# 04_GIRIS_CIKIS_EMG_BUTTONS.net
KiCad netlist of a schematic drawn in Altium Designer
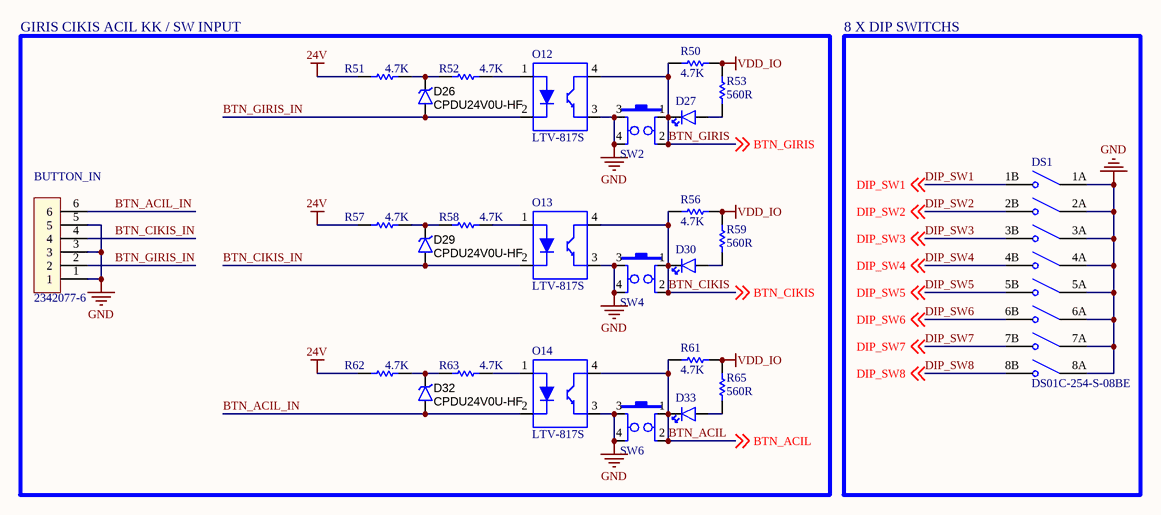
[diagram p0: 04_GIRIS_CIKIS_EMG_BUTTONS.SchDoc]

(export (version "E")
  (design (tool "Eeschema 10.0.6"))
  (components
    (comp (ref "BUTTON_IN")
      (value "2342077-6")
      (footprint "TERM BLOCK HDR 6POS 90DEG PITCH 3.81MM")
      (fields
        (field (name "DIGI-KEY PART NUMBER") "A145325-ND")
        (field (name "MANUFACTURER") "TE Connectivity AMP Connectors")
      )
      (libsource (lib "FKDZ_Altium_Lib") (part "TERM BLOCK HDR 6POS 90DEG 3.81MM"))
    )
    (comp (ref "D26")
      (value "CPDU24V0U-HF")
      (footprint "SOD523F")
      (description "50V Clamp 3A (8/20µs) Ipp Tvs Diode Surface Mount 0603/SOD-523F")
      (fields
        (field (name "DIGI-KEY PART NUMBER") "641-1679-1-ND")
        (field (name "MANUFACTURER") "Comchip Technology")
      )
      (libsource (lib "FKDZ_Altium_Lib") (part "TVS DIODE 24VWM 50V 0603/SOD523F CPDU24V0U-HF"))
    )
    (comp (ref "D27")
      (value "led_green")
      (footprint "805LED")
      (description "LED 2X1.2MM 570NM GN WTR CLR SMD")
      (fields (field (name "DIGI-KEY PART NUMBER") "754-1127-1-ND"))
      (libsource (lib "FKDZ_Altium_Lib") (part "LED_GREEN_0805"))
    )
    (comp (ref "D29")
      (value "CPDU24V0U-HF")
      (footprint "SOD523F")
      (description "50V Clamp 3A (8/20µs) Ipp Tvs Diode Surface Mount 0603/SOD-523F")
      (fields
        (field (name "DIGI-KEY PART NUMBER") "641-1679-1-ND")
        (field (name "MANUFACTURER") "Comchip Technology")
      )
      (libsource (lib "FKDZ_Altium_Lib") (part "TVS DIODE 24VWM 50V 0603/SOD523F CPDU24V0U-HF"))
    )
    (comp (ref "D30")
      (value "led_green")
      (footprint "805LED")
      (description "LED 2X1.2MM 570NM GN WTR CLR SMD")
      (fields (field (name "DIGI-KEY PART NUMBER") "754-1127-1-ND"))
      (libsource (lib "FKDZ_Altium_Lib") (part "LED_GREEN_0805"))
    )
    (comp (ref "D32")
      (value "CPDU24V0U-HF")
      (footprint "SOD523F")
      (description "50V Clamp 3A (8/20µs) Ipp Tvs Diode Surface Mount 0603/SOD-523F")
      (fields
        (field (name "DIGI-KEY PART NUMBER") "641-1679-1-ND")
        (field (name "MANUFACTURER") "Comchip Technology")
      )
      (libsource (lib "FKDZ_Altium_Lib") (part "TVS DIODE 24VWM 50V 0603/SOD523F CPDU24V0U-HF"))
    )
    (comp (ref "D33")
      (value "led_green")
      (footprint "805LED")
      (description "LED 2X1.2MM 570NM GN WTR CLR SMD")
      (fields (field (name "DIGI-KEY PART NUMBER") "754-1127-1-ND"))
      (libsource (lib "FKDZ_Altium_Lib") (part "LED_GREEN_0805"))
    )
    (comp (ref "DS1")
      (value "DS01C-254-S-08BE")
      (footprint "SW_DS01C-254-S-08BE")
      (description "Dip Switch SPST 8 Position Through Hole Slide (Standard) Actuator 25mA 24VDC")
      (fields (field (name "DIGI-KEY PART NUMBER") "2223-DS01C-254-S-08BE-ND"))
      (libsource (lib "FKDZ_Altium_Lib") (part "DIP SWITCH, SPST, 2.54 PITCH, RA DS01C-254-S-08BE"))
    )
    (comp (ref "O12")
      (value "LTV-817S")
      (footprint "SMD4-2.54-4.6X6.5MM")
      (description "Optoisolator Transistor Output 5000Vrms 1 Channel 4-SMD")
      (fields (field (name "DIGI-KEY PART NUMBER") "160-1367-5-ND"))
      (libsource (lib "FKDZ_Altium_Lib") (part "OPTOISOLATR 5KV TRANSISTOR 4-SMD LTV-817S"))
    )
    (comp (ref "O13")
      (value "LTV-817S")
      (footprint "SMD4-2.54-4.6X6.5MM")
      (description "Optoisolator Transistor Output 5000Vrms 1 Channel 4-SMD")
      (fields (field (name "DIGI-KEY PART NUMBER") "160-1367-5-ND"))
      (libsource (lib "FKDZ_Altium_Lib") (part "OPTOISOLATR 5KV TRANSISTOR 4-SMD LTV-817S"))
    )
    (comp (ref "O14")
      (value "LTV-817S")
      (footprint "SMD4-2.54-4.6X6.5MM")
      (description "Optoisolator Transistor Output 5000Vrms 1 Channel 4-SMD")
      (fields (field (name "DIGI-KEY PART NUMBER") "160-1367-5-ND"))
      (libsource (lib "FKDZ_Altium_Lib") (part "OPTOISOLATR 5KV TRANSISTOR 4-SMD LTV-817S"))
    )
    (comp (ref "R50")
      (value "4.7K")
      (footprint "603R")
      (description "4.7 kOhms ±5% 0.1W, 1/10W Chip Resistor 0603 (1608 Metric) Moisture Resistant Thick Film")
      (fields (field (name "DIGI-KEY PART NUMBER") "311-4.7KGRTR-ND") (field (name "MANUFACTURER") "Yageo"))
      (libsource (lib "FKDZ_Altium_Lib") (part "RES_4.7K_OHM_%5_0.1W_0603"))
    )
    (comp (ref "R51")
      (value "4.7K")
      (footprint "603R")
      (description "4.7 kOhms ±5% 0.1W, 1/10W Chip Resistor 0603 (1608 Metric) Moisture Resistant Thick Film")
      (fields (field (name "DIGI-KEY PART NUMBER") "311-4.7KGRTR-ND") (field (name "MANUFACTURER") "Yageo"))
      (libsource (lib "FKDZ_Altium_Lib") (part "RES_4.7K_OHM_%5_0.1W_0603"))
    )
    (comp (ref "R52")
      (value "4.7K")
      (footprint "603R")
      (description "4.7 kOhms ±5% 0.1W, 1/10W Chip Resistor 0603 (1608 Metric) Moisture Resistant Thick Film")
      (fields (field (name "DIGI-KEY PART NUMBER") "311-4.7KGRTR-ND") (field (name "MANUFACTURER") "Yageo"))
      (libsource (lib "FKDZ_Altium_Lib") (part "RES_4.7K_OHM_%5_0.1W_0603"))
    )
    (comp (ref "R53")
      (value "560R")
      (footprint "603R")
      (description "560 Ohms ±5% 0.1W, 1/10W Chip Resistor 0603 (1608 Metric) Moisture Resistant Thick Film")
      (fields (field (name "DIGI-KEY PART NUMBER") "311-560GRCT-ND") (field (name "MANUFACTURER") "Yageo"))
      (libsource (lib "FKDZ_Altium_Lib") (part "RES_560_OHM_%5_0.1W_0603"))
    )
    (comp (ref "R56")
      (value "4.7K")
      (footprint "603R")
      (description "4.7 kOhms ±5% 0.1W, 1/10W Chip Resistor 0603 (1608 Metric) Moisture Resistant Thick Film")
      (fields (field (name "DIGI-KEY PART NUMBER") "311-4.7KGRTR-ND") (field (name "MANUFACTURER") "Yageo"))
      (libsource (lib "FKDZ_Altium_Lib") (part "RES_4.7K_OHM_%5_0.1W_0603"))
    )
    (comp (ref "R57")
      (value "4.7K")
      (footprint "603R")
      (description "4.7 kOhms ±5% 0.1W, 1/10W Chip Resistor 0603 (1608 Metric) Moisture Resistant Thick Film")
      (fields (field (name "DIGI-KEY PART NUMBER") "311-4.7KGRTR-ND") (field (name "MANUFACTURER") "Yageo"))
      (libsource (lib "FKDZ_Altium_Lib") (part "RES_4.7K_OHM_%5_0.1W_0603"))
    )
    (comp (ref "R58")
      (value "4.7K")
      (footprint "603R")
      (description "4.7 kOhms ±5% 0.1W, 1/10W Chip Resistor 0603 (1608 Metric) Moisture Resistant Thick Film")
      (fields (field (name "DIGI-KEY PART NUMBER") "311-4.7KGRTR-ND") (field (name "MANUFACTURER") "Yageo"))
      (libsource (lib "FKDZ_Altium_Lib") (part "RES_4.7K_OHM_%5_0.1W_0603"))
    )
    (comp (ref "R59")
      (value "560R")
      (footprint "603R")
      (description "560 Ohms ±5% 0.1W, 1/10W Chip Resistor 0603 (1608 Metric) Moisture Resistant Thick Film")
      (fields (field (name "DIGI-KEY PART NUMBER") "311-560GRCT-ND") (field (name "MANUFACTURER") "Yageo"))
      (libsource (lib "FKDZ_Altium_Lib") (part "RES_560_OHM_%5_0.1W_0603"))
    )
    (comp (ref "R61")
      (value "4.7K")
      (footprint "603R")
      (description "4.7 kOhms ±5% 0.1W, 1/10W Chip Resistor 0603 (1608 Metric) Moisture Resistant Thick Film")
      (fields (field (name "DIGI-KEY PART NUMBER") "311-4.7KGRTR-ND") (field (name "MANUFACTURER") "Yageo"))
      (libsource (lib "FKDZ_Altium_Lib") (part "RES_4.7K_OHM_%5_0.1W_0603"))
    )
    (comp (ref "R62")
      (value "4.7K")
      (footprint "603R")
      (description "4.7 kOhms ±5% 0.1W, 1/10W Chip Resistor 0603 (1608 Metric) Moisture Resistant Thick Film")
      (fields (field (name "DIGI-KEY PART NUMBER") "311-4.7KGRTR-ND") (field (name "MANUFACTURER") "Yageo"))
      (libsource (lib "FKDZ_Altium_Lib") (part "RES_4.7K_OHM_%5_0.1W_0603"))
    )
    (comp (ref "R63")
      (value "4.7K")
      (footprint "603R")
      (description "4.7 kOhms ±5% 0.1W, 1/10W Chip Resistor 0603 (1608 Metric) Moisture Resistant Thick Film")
      (fields (field (name "DIGI-KEY PART NUMBER") "311-4.7KGRTR-ND") (field (name "MANUFACTURER") "Yageo"))
      (libsource (lib "FKDZ_Altium_Lib") (part "RES_4.7K_OHM_%5_0.1W_0603"))
    )
    (comp (ref "R65")
      (value "560R")
      (footprint "603R")
      (description "560 Ohms ±5% 0.1W, 1/10W Chip Resistor 0603 (1608 Metric) Moisture Resistant Thick Film")
      (fields (field (name "DIGI-KEY PART NUMBER") "311-560GRCT-ND") (field (name "MANUFACTURER") "Yageo"))
      (libsource (lib "FKDZ_Altium_Lib") (part "RES_560_OHM_%5_0.1W_0603"))
    )
    (comp (ref "SW2")
      (value "switch tactile")
      (footprint "SW_TACTILE_6X6mm SMT")
      (description "Tactile Switch SPST-NO Top Actuated Surface Mount")
      (fields (field (name "DIGI-KEY PART NUMBER") "CKN9112TR-ND"))
      (libsource (lib "FKDZ_Altium_Lib") (part "SW_TACTILE_6x6x4.3mm SMT"))
    )
    (comp (ref "SW4")
      (value "switch tactile")
      (footprint "SW_TACTILE_6X6mm SMT")
      (description "Tactile Switch SPST-NO Top Actuated Surface Mount")
      (fields (field (name "DIGI-KEY PART NUMBER") "CKN9112TR-ND"))
      (libsource (lib "FKDZ_Altium_Lib") (part "SW_TACTILE_6x6x4.3mm SMT"))
    )
    (comp (ref "SW6")
      (value "switch tactile")
      (footprint "SW_TACTILE_6X6mm SMT")
      (description "Tactile Switch SPST-NO Top Actuated Surface Mount")
      (fields (field (name "DIGI-KEY PART NUMBER") "CKN9112TR-ND"))
      (libsource (lib "FKDZ_Altium_Lib") (part "SW_TACTILE_6x6x4.3mm SMT"))
    )
  )
  (nets
    (net (code "1") (name "/BTN_ACIL_IN") (class "Default")
      (node (ref "BUTTON_IN") (pin "6") (pinfunction "6_6") (pintype "passive"))
      (node (ref "D32") (pin "1") (pinfunction "1_1") (pintype "passive"))
      (node (ref "O14") (pin "2") (pinfunction "CATHODE_2") (pintype "passive"))
    )
    (net (code "2") (name "/BTN_CIKIS_IN") (class "Default")
      (node (ref "BUTTON_IN") (pin "4") (pinfunction "4_4") (pintype "passive"))
      (node (ref "D29") (pin "1") (pinfunction "1_1") (pintype "passive"))
      (node (ref "O13") (pin "2") (pinfunction "CATHODE_2") (pintype "passive"))
    )
    (net (code "3") (name "/BTN_GIRIS_IN") (class "Default")
      (node (ref "BUTTON_IN") (pin "2") (pinfunction "2_2") (pintype "passive"))
      (node (ref "D26") (pin "1") (pinfunction "1_1") (pintype "passive"))
      (node (ref "O12") (pin "2") (pinfunction "CATHODE_2") (pintype "passive"))
    )
    (net (code "4") (name "24V") (class "Default")
      (node (ref "R51") (pin "1") (pinfunction "1_1") (pintype "passive"))
      (node (ref "R57") (pin "1") (pinfunction "1_1") (pintype "passive"))
      (node (ref "R62") (pin "1") (pinfunction "1_1") (pintype "passive"))
    )
    (net (code "5") (name "BTN_ACIL") (class "Default")
      (node (ref "D33") (pin "2") (pinfunction "K_2") (pintype "passive"))
      (node (ref "O14") (pin "4") (pinfunction "COLLECTOR_4") (pintype "passive"))
      (node (ref "R61") (pin "1") (pinfunction "1_1") (pintype "passive"))
      (node (ref "SW6") (pin "1") (pinfunction "1_1") (pintype "passive"))
      (node (ref "SW6") (pin "2") (pinfunction "2_2") (pintype "passive"))
    )
    (net (code "6") (name "BTN_CIKIS") (class "Default")
      (node (ref "D30") (pin "2") (pinfunction "K_2") (pintype "passive"))
      (node (ref "O13") (pin "4") (pinfunction "COLLECTOR_4") (pintype "passive"))
      (node (ref "R56") (pin "1") (pinfunction "1_1") (pintype "passive"))
      (node (ref "SW4") (pin "1") (pinfunction "1_1") (pintype "passive"))
      (node (ref "SW4") (pin "2") (pinfunction "2_2") (pintype "passive"))
    )
    (net (code "7") (name "BTN_GIRIS") (class "Default")
      (node (ref "D27") (pin "2") (pinfunction "K_2") (pintype "passive"))
      (node (ref "O12") (pin "4") (pinfunction "COLLECTOR_4") (pintype "passive"))
      (node (ref "R50") (pin "1") (pinfunction "1_1") (pintype "passive"))
      (node (ref "SW2") (pin "1") (pinfunction "1_1") (pintype "passive"))
      (node (ref "SW2") (pin "2") (pinfunction "2_2") (pintype "passive"))
    )
    (net (code "8") (name "DIP_SW1") (class "Default")
      (node (ref "DS1") (pin "1B") (pinfunction "NO1_1B") (pintype "passive"))
    )
    (net (code "9") (name "DIP_SW2") (class "Default")
      (node (ref "DS1") (pin "2B") (pinfunction "NO2_2B") (pintype "passive"))
    )
    (net (code "10") (name "DIP_SW3") (class "Default")
      (node (ref "DS1") (pin "3B") (pinfunction "NO3_3B") (pintype "passive"))
    )
    (net (code "11") (name "DIP_SW4") (class "Default")
      (node (ref "DS1") (pin "4B") (pinfunction "NO4_4B") (pintype "passive"))
    )
    (net (code "12") (name "DIP_SW5") (class "Default")
      (node (ref "DS1") (pin "5B") (pinfunction "NO5_5B") (pintype "passive"))
    )
    (net (code "13") (name "DIP_SW6") (class "Default")
      (node (ref "DS1") (pin "6B") (pinfunction "NO6_6B") (pintype "passive"))
    )
    (net (code "14") (name "DIP_SW7") (class "Default")
      (node (ref "DS1") (pin "7B") (pinfunction "NO7_7B") (pintype "passive"))
    )
    (net (code "15") (name "DIP_SW8") (class "Default")
      (node (ref "DS1") (pin "8B") (pinfunction "NO8_8B") (pintype "passive"))
    )
    (net (code "16") (name "GND") (class "Default")
      (node (ref "BUTTON_IN") (pin "1") (pinfunction "1_1") (pintype "passive"))
      (node (ref "BUTTON_IN") (pin "3") (pinfunction "3_3") (pintype "passive"))
      (node (ref "BUTTON_IN") (pin "5") (pinfunction "5_5") (pintype "passive"))
      (node (ref "DS1") (pin "1A") (pinfunction "COM1_1A") (pintype "passive"))
      (node (ref "DS1") (pin "2A") (pinfunction "COM2_2A") (pintype "passive"))
      (node (ref "DS1") (pin "3A") (pinfunction "COM3_3A") (pintype "passive"))
      (node (ref "DS1") (pin "4A") (pinfunction "COM4_4A") (pintype "passive"))
      (node (ref "DS1") (pin "5A") (pinfunction "COM5_5A") (pintype "passive"))
      (node (ref "DS1") (pin "6A") (pinfunction "COM6_6A") (pintype "passive"))
      (node (ref "DS1") (pin "7A") (pinfunction "COM7_7A") (pintype "passive"))
      (node (ref "DS1") (pin "8A") (pinfunction "COM8_8A") (pintype "passive"))
      (node (ref "O12") (pin "3") (pinfunction "EMITER_3") (pintype "passive"))
      (node (ref "O13") (pin "3") (pinfunction "EMITER_3") (pintype "passive"))
      (node (ref "O14") (pin "3") (pinfunction "EMITER_3") (pintype "passive"))
      (node (ref "SW2") (pin "3") (pinfunction "3_3") (pintype "passive"))
      (node (ref "SW2") (pin "4") (pinfunction "4_4") (pintype "passive"))
      (node (ref "SW4") (pin "3") (pinfunction "3_3") (pintype "passive"))
      (node (ref "SW4") (pin "4") (pinfunction "4_4") (pintype "passive"))
      (node (ref "SW6") (pin "3") (pinfunction "3_3") (pintype "passive"))
      (node (ref "SW6") (pin "4") (pinfunction "4_4") (pintype "passive"))
    )
    (net (code "17") (name "Net-(D26-Pad2)") (class "Default")
      (node (ref "D26") (pin "2") (pinfunction "2_2") (pintype "passive"))
      (node (ref "R51") (pin "2") (pinfunction "2_2") (pintype "passive"))
      (node (ref "R52") (pin "1") (pinfunction "1_1") (pintype "passive"))
    )
    (net (code "18") (name "Net-(D27-A)") (class "Default")
      (node (ref "D27") (pin "1") (pinfunction "A_1") (pintype "passive"))
      (node (ref "R53") (pin "1") (pinfunction "1_1") (pintype "passive"))
    )
    (net (code "19") (name "Net-(D29-Pad2)") (class "Default")
      (node (ref "D29") (pin "2") (pinfunction "2_2") (pintype "passive"))
      (node (ref "R57") (pin "2") (pinfunction "2_2") (pintype "passive"))
      (node (ref "R58") (pin "1") (pinfunction "1_1") (pintype "passive"))
    )
    (net (code "20") (name "Net-(D30-A)") (class "Default")
      (node (ref "D30") (pin "1") (pinfunction "A_1") (pintype "passive"))
      (node (ref "R59") (pin "1") (pinfunction "1_1") (pintype "passive"))
    )
    (net (code "21") (name "Net-(D32-Pad2)") (class "Default")
      (node (ref "D32") (pin "2") (pinfunction "2_2") (pintype "passive"))
      (node (ref "R62") (pin "2") (pinfunction "2_2") (pintype "passive"))
      (node (ref "R63") (pin "1") (pinfunction "1_1") (pintype "passive"))
    )
    (net (code "22") (name "Net-(D33-A)") (class "Default")
      (node (ref "D33") (pin "1") (pinfunction "A_1") (pintype "passive"))
      (node (ref "R65") (pin "1") (pinfunction "1_1") (pintype "passive"))
    )
    (net (code "23") (name "Net-(O12-ANODE)") (class "Default")
      (node (ref "O12") (pin "1") (pinfunction "ANODE_1") (pintype "passive"))
      (node (ref "R52") (pin "2") (pinfunction "2_2") (pintype "passive"))
    )
    (net (code "24") (name "Net-(O13-ANODE)") (class "Default")
      (node (ref "O13") (pin "1") (pinfunction "ANODE_1") (pintype "passive"))
      (node (ref "R58") (pin "2") (pinfunction "2_2") (pintype "passive"))
    )
    (net (code "25") (name "Net-(O14-ANODE)") (class "Default")
      (node (ref "O14") (pin "1") (pinfunction "ANODE_1") (pintype "passive"))
      (node (ref "R63") (pin "2") (pinfunction "2_2") (pintype "passive"))
    )
    (net (code "26") (name "VDD_IO") (class "Default")
      (node (ref "R50") (pin "2") (pinfunction "2_2") (pintype "passive"))
      (node (ref "R53") (pin "2") (pinfunction "2_2") (pintype "passive"))
      (node (ref "R56") (pin "2") (pinfunction "2_2") (pintype "passive"))
      (node (ref "R59") (pin "2") (pinfunction "2_2") (pintype "passive"))
      (node (ref "R61") (pin "2") (pinfunction "2_2") (pintype "passive"))
      (node (ref "R65") (pin "2") (pinfunction "2_2") (pintype "passive"))
    )
  )
)
